# SPDT_eval.net
KiCad netlist of a schematic drawn in EAGLE
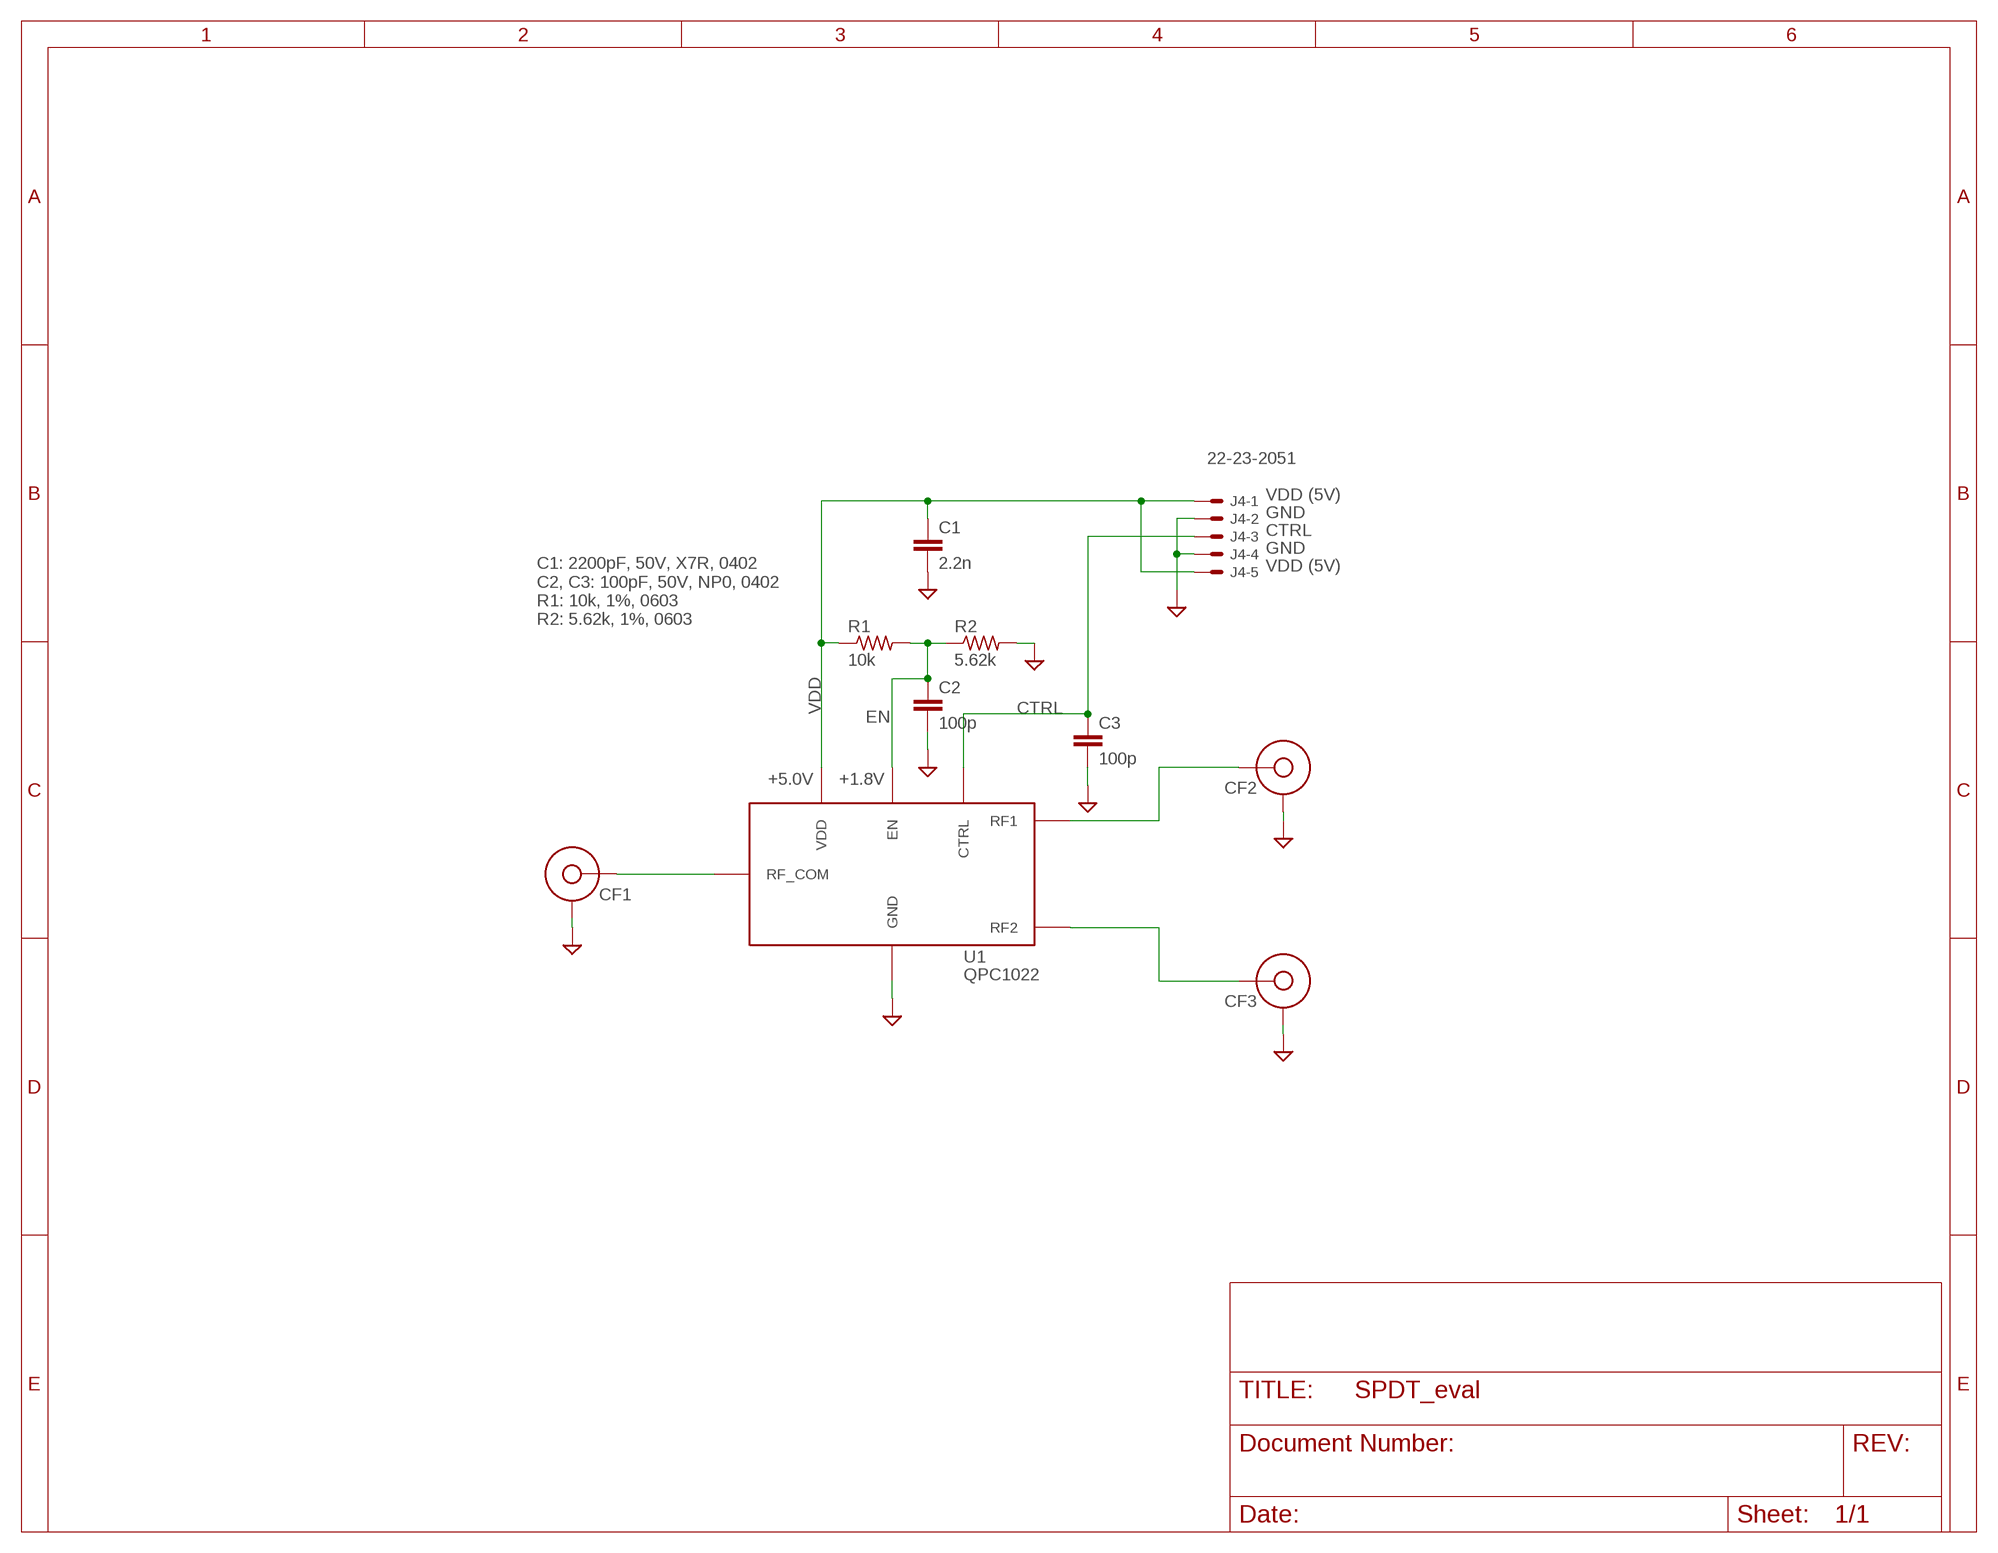
[diagram p0: schematic, sheet 1]

(export (version "E")
  (design (tool "Eeschema 10.0.6"))
  (components
    (comp (ref "C1")
      (value "2.2n")
      (footprint "eagle-import:.0402-B-NOSILK")
      (libsource (lib "eagle-import") (part "C-EU0402-B-NOSILK"))
    )
    (comp (ref "C2")
      (value "100p")
      (footprint "eagle-import:.0402-B-NOSILK")
      (libsource (lib "eagle-import") (part "C-EU0402-B-NOSILK"))
    )
    (comp (ref "C3")
      (value "100p")
      (footprint "eagle-import:.0402-B-NOSILK")
      (libsource (lib "eagle-import") (part "C-EU0402-B-NOSILK"))
    )
    (comp (ref "CF1")
      (value "SMA-CINCH-END-FIRE")
      (footprint "eagle-import:SMAJ716-ND")
      (libsource (lib "eagle-import") (part "SMA-CINCH-END-FIRE"))
    )
    (comp (ref "CF2")
      (value "SMA-CINCH-END-FIRE")
      (footprint "eagle-import:SMAJ716-ND")
      (libsource (lib "eagle-import") (part "SMA-CINCH-END-FIRE"))
    )
    (comp (ref "CF3")
      (value "SMA-CINCH-END-FIRE")
      (footprint "eagle-import:SMAJ716-ND")
      (libsource (lib "eagle-import") (part "SMA-CINCH-END-FIRE"))
    )
    (comp (ref "J4")
      (value "22-23-2051")
      (footprint "eagle-import:22-23-2051")
      (fields (field (name "MF") "MOLEX"))
      (libsource (lib "eagle-import") (part "22-23-2051"))
    )
    (comp (ref "R1")
      (value "10k")
      (footprint "eagle-import:.0603-B-NOSILK")
      (libsource (lib "eagle-import") (part "R-US_0603-B-NOSILK"))
    )
    (comp (ref "R2")
      (value "5.62k")
      (footprint "eagle-import:.0603-B-NOSILK")
      (libsource (lib "eagle-import") (part "R-US_0603-B-NOSILK"))
    )
    (comp (ref "U1")
      (value "QPC1022")
      (footprint "eagle-import:QPC1022")
      (libsource (lib "eagle-import") (part "QPC1022"))
    )
  )
  (nets
    (net (code "1") (name "/CTRL") (class "Default")
      (node (ref "C3") (pin "1") (pinfunction "1_1") (pintype "passive"))
      (node (ref "J4") (pin "3") (pinfunction "S_3") (pintype "passive"))
      (node (ref "U1") (pin "CTRL") (pinfunction "CTRL_CTRL") (pintype "bidirectional"))
    )
    (net (code "2") (name "/EN") (class "Default")
      (node (ref "C2") (pin "1") (pinfunction "1_1") (pintype "passive"))
      (node (ref "R1") (pin "2") (pinfunction "2_2") (pintype "passive"))
      (node (ref "R2") (pin "1") (pinfunction "1_1") (pintype "passive"))
      (node (ref "U1") (pin "EN") (pinfunction "EN_EN") (pintype "bidirectional"))
    )
    (net (code "3") (name "/VDD") (class "Default")
      (node (ref "C1") (pin "1") (pinfunction "1_1") (pintype "passive"))
      (node (ref "J4") (pin "1") (pinfunction "S_1") (pintype "passive"))
      (node (ref "J4") (pin "5") (pinfunction "S_5") (pintype "passive"))
      (node (ref "R1") (pin "1") (pinfunction "1_1") (pintype "passive"))
      (node (ref "U1") (pin "VDD") (pinfunction "VDD_VDD") (pintype "bidirectional"))
    )
    (net (code "4") (name "GND") (class "Default")
      (node (ref "C1") (pin "2") (pinfunction "2_2") (pintype "passive"))
      (node (ref "C2") (pin "2") (pinfunction "2_2") (pintype "passive"))
      (node (ref "C3") (pin "2") (pinfunction "2_2") (pintype "passive"))
      (node (ref "CF1") (pin "GND1") (pinfunction "GND_GND1") (pintype "power_in"))
      (node (ref "CF1") (pin "GND2") (pinfunction "GND_GND2") (pintype "power_in"))
      (node (ref "CF1") (pin "GND3") (pinfunction "GND_GND3") (pintype "power_in"))
      (node (ref "CF1") (pin "GND4") (pinfunction "GND_GND4") (pintype "power_in"))
      (node (ref "CF2") (pin "GND1") (pinfunction "GND_GND1") (pintype "power_in"))
      (node (ref "CF2") (pin "GND2") (pinfunction "GND_GND2") (pintype "power_in"))
      (node (ref "CF2") (pin "GND3") (pinfunction "GND_GND3") (pintype "power_in"))
      (node (ref "CF2") (pin "GND4") (pinfunction "GND_GND4") (pintype "power_in"))
      (node (ref "CF3") (pin "GND1") (pinfunction "GND_GND1") (pintype "power_in"))
      (node (ref "CF3") (pin "GND2") (pinfunction "GND_GND2") (pintype "power_in"))
      (node (ref "CF3") (pin "GND3") (pinfunction "GND_GND3") (pintype "power_in"))
      (node (ref "CF3") (pin "GND4") (pinfunction "GND_GND4") (pintype "power_in"))
      (node (ref "J4") (pin "2") (pinfunction "S_2") (pintype "passive"))
      (node (ref "J4") (pin "4") (pinfunction "S_4") (pintype "passive"))
      (node (ref "R2") (pin "2") (pinfunction "2_2") (pintype "passive"))
      (node (ref "U1") (pin "GND@1") (pinfunction "GND_GND@1") (pintype "bidirectional"))
      (node (ref "U1") (pin "GND@2") (pinfunction "GND_GND@2") (pintype "bidirectional"))
      (node (ref "U1") (pin "GND@3") (pinfunction "GND_GND@3") (pintype "bidirectional"))
    )
    (net (code "5") (name "Net-(CF1-CENTERCONDUCTOR)") (class "Default")
      (node (ref "CF1") (pin "P$3") (pinfunction "CENTERCONDUCTOR_P$3") (pintype "bidirectional"))
      (node (ref "U1") (pin "ANT") (pinfunction "RF_COM_ANT") (pintype "bidirectional"))
    )
    (net (code "6") (name "Net-(CF2-CENTERCONDUCTOR)") (class "Default")
      (node (ref "CF2") (pin "P$3") (pinfunction "CENTERCONDUCTOR_P$3") (pintype "bidirectional"))
      (node (ref "U1") (pin "RF1") (pinfunction "RF1_RF1") (pintype "bidirectional"))
    )
    (net (code "7") (name "Net-(CF3-CENTERCONDUCTOR)") (class "Default")
      (node (ref "CF3") (pin "P$3") (pinfunction "CENTERCONDUCTOR_P$3") (pintype "bidirectional"))
      (node (ref "U1") (pin "RF2") (pinfunction "RF2_RF2") (pintype "bidirectional"))
    )
  )
)
